# pcb-bldc-servo-2.net
KiCad netlist of a schematic drawn in EAGLE
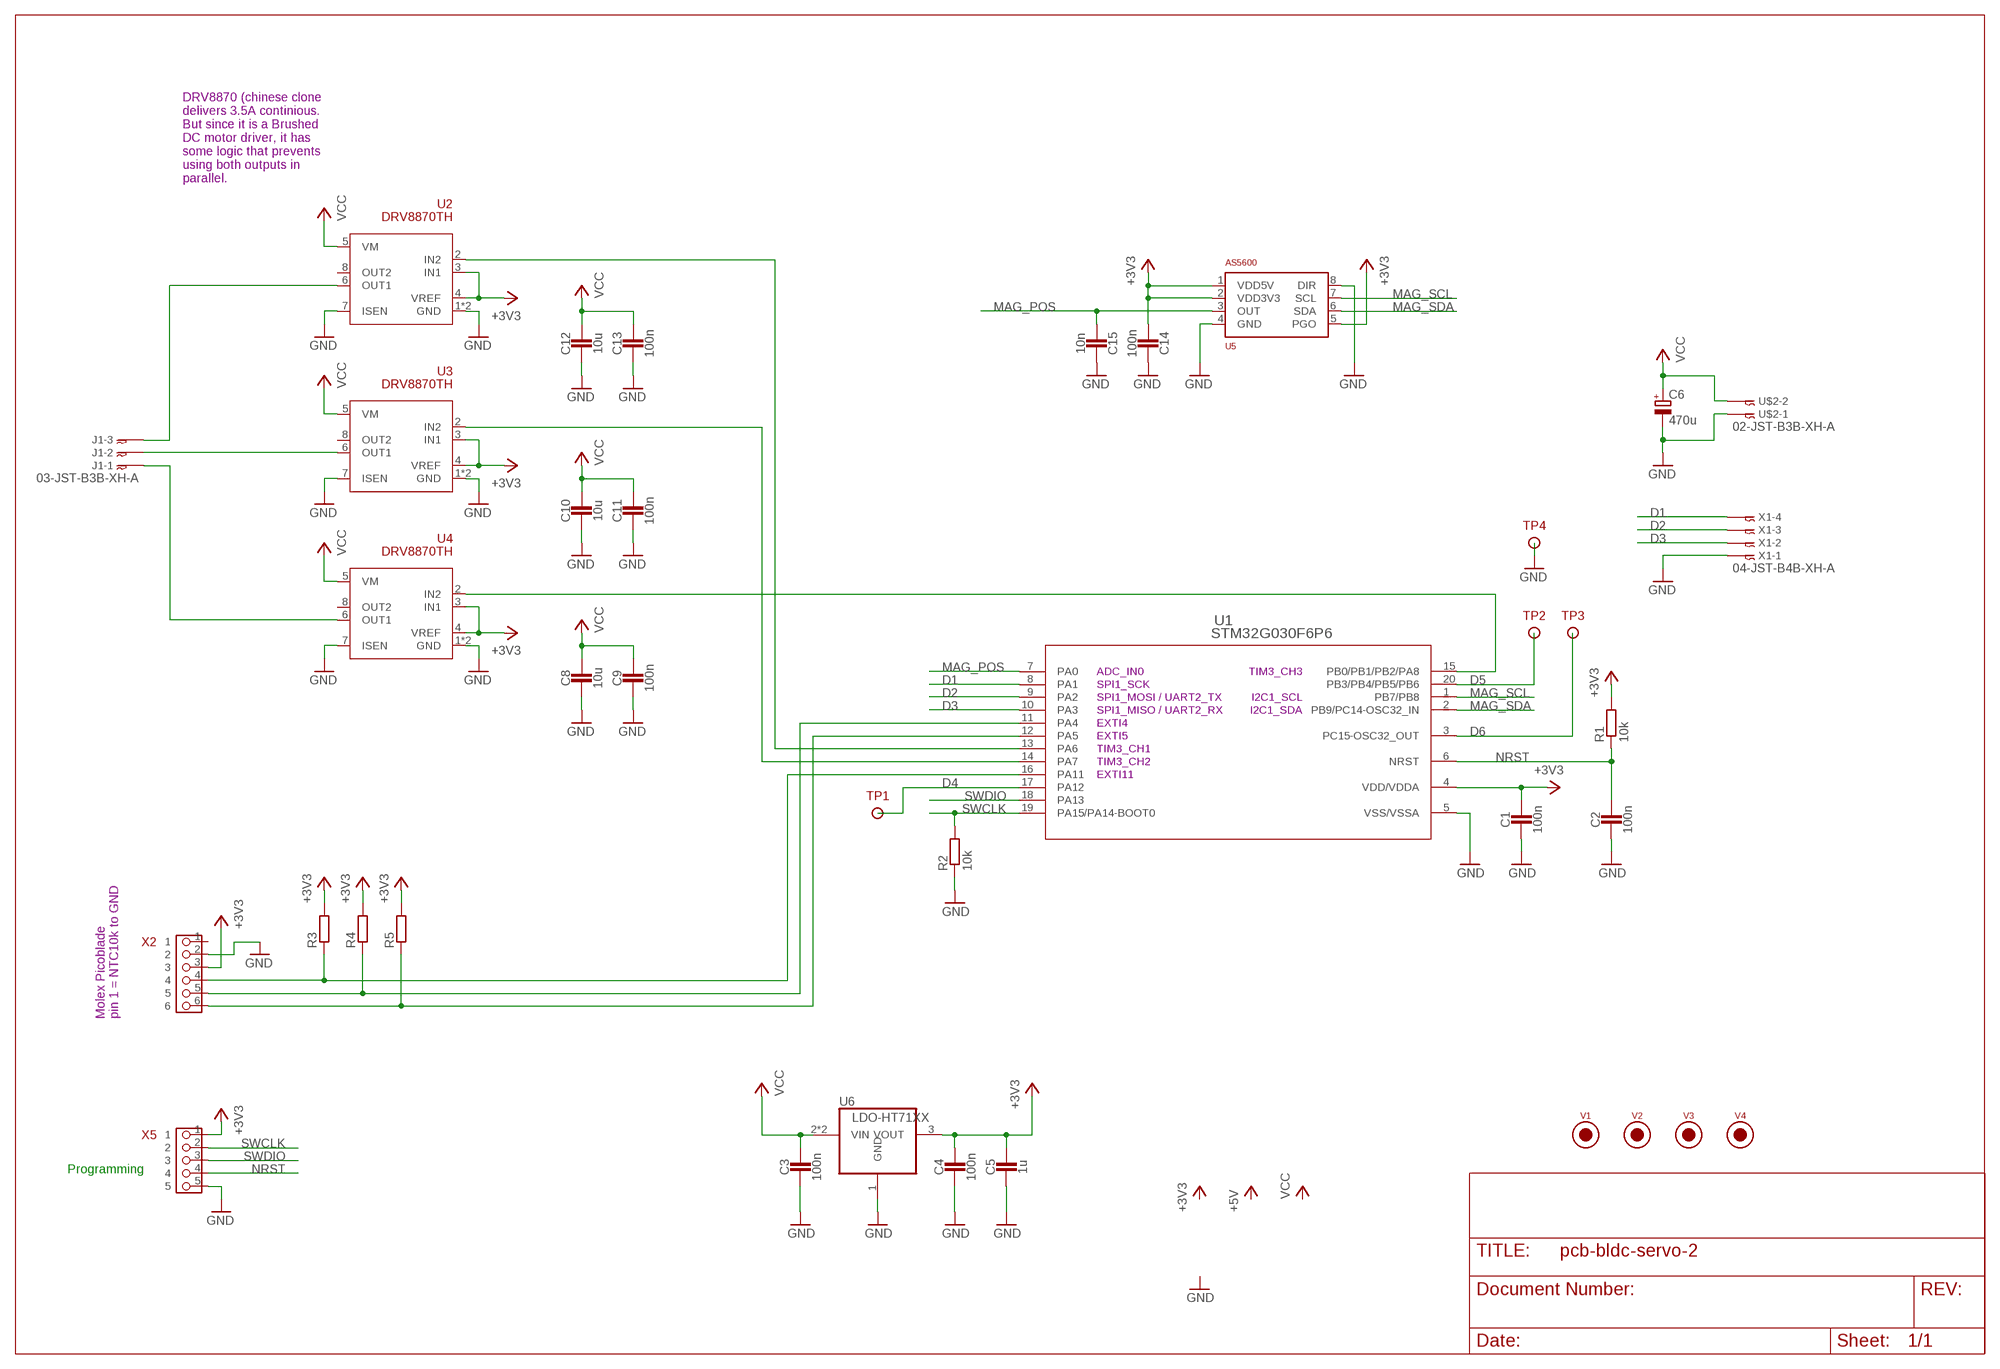
[diagram p0: schematic, sheet 1]

(export (version "E")
  (design (tool "Eeschema 10.0.6"))
  (components
    (comp (ref "C1")
      (value "100n")
      (footprint "eagle-import:0603_CAP")
      (libsource (lib "eagle-import") (part "CAPACITOR0603_CAP"))
    )
    (comp (ref "C2")
      (value "100n")
      (footprint "eagle-import:0603_CAP")
      (libsource (lib "eagle-import") (part "CAPACITOR0603_CAP"))
    )
    (comp (ref "C3")
      (value "100n")
      (footprint "eagle-import:0603_CAP")
      (libsource (lib "eagle-import") (part "CAPACITOR0603_CAP"))
    )
    (comp (ref "C4")
      (value "100n")
      (footprint "eagle-import:0603_CAP")
      (libsource (lib "eagle-import") (part "CAPACITOR0603_CAP"))
    )
    (comp (ref "C5")
      (value "1u")
      (footprint "eagle-import:0603_CAP")
      (libsource (lib "eagle-import") (part "CAPACITOR0603_CAP"))
    )
    (comp (ref "C6")
      (value "470u")
      (footprint "eagle-import:153CLV-1010")
      (libsource (lib "eagle-import") (part "CPOL-EU153CLV-1010"))
    )
    (comp (ref "C8")
      (value "10u")
      (footprint "eagle-import:1206_CAP")
      (libsource (lib "eagle-import") (part "CAPACITOR1206_CAP"))
    )
    (comp (ref "C9")
      (value "100n")
      (footprint "eagle-import:0603_CAP")
      (libsource (lib "eagle-import") (part "CAPACITOR0603_CAP"))
    )
    (comp (ref "C10")
      (value "10u")
      (footprint "eagle-import:1206_CAP")
      (libsource (lib "eagle-import") (part "CAPACITOR1206_CAP"))
    )
    (comp (ref "C11")
      (value "100n")
      (footprint "eagle-import:0603_CAP")
      (libsource (lib "eagle-import") (part "CAPACITOR0603_CAP"))
    )
    (comp (ref "C12")
      (value "10u")
      (footprint "eagle-import:1206_CAP")
      (libsource (lib "eagle-import") (part "CAPACITOR1206_CAP"))
    )
    (comp (ref "C13")
      (value "100n")
      (footprint "eagle-import:0603_CAP")
      (libsource (lib "eagle-import") (part "CAPACITOR0603_CAP"))
    )
    (comp (ref "C14")
      (value "100n")
      (footprint "eagle-import:0603_CAP")
      (libsource (lib "eagle-import") (part "CAPACITOR0603_CAP"))
    )
    (comp (ref "C15")
      (value "10n")
      (footprint "eagle-import:0603_CAP")
      (libsource (lib "eagle-import") (part "CAPACITOR0603_CAP"))
    )
    (comp (ref "J1")
      (value "03-JST-B3B-XH-A")
      (footprint "eagle-import:B3B-XH")
      (libsource (lib "eagle-import") (part "03-JST-B3B-XH-A"))
    )
    (comp (ref "R1")
      (value "10k")
      (footprint "eagle-import:0603-RES")
      (libsource (lib "eagle-import") (part "RESISTOR0603_RES"))
    )
    (comp (ref "R2")
      (value "10k")
      (footprint "eagle-import:0603-RES")
      (libsource (lib "eagle-import") (part "RESISTOR0603_RES"))
    )
    (comp (ref "R3")
      (value "RESISTOR0603_RES")
      (footprint "eagle-import:0603-RES")
      (libsource (lib "eagle-import") (part "RESISTOR0603_RES"))
    )
    (comp (ref "R4")
      (value "RESISTOR0603_RES")
      (footprint "eagle-import:0603-RES")
      (libsource (lib "eagle-import") (part "RESISTOR0603_RES"))
    )
    (comp (ref "R5")
      (value "RESISTOR0603_RES")
      (footprint "eagle-import:0603-RES")
      (libsource (lib "eagle-import") (part "RESISTOR0603_RES"))
    )
    (comp (ref "TP1")
      (value "TESTPIN1MM")
      (footprint "eagle-import:PIN-SMD-1X1-TEST_1M0")
      (libsource (lib "eagle-import") (part "TESTPIN1MM"))
    )
    (comp (ref "TP2")
      (value "TESTPIN1MM")
      (footprint "eagle-import:PIN-SMD-1X1-TEST_1M0")
      (libsource (lib "eagle-import") (part "TESTPIN1MM"))
    )
    (comp (ref "TP3")
      (value "TESTPIN1MM")
      (footprint "eagle-import:PIN-SMD-1X1-TEST_1M0")
      (libsource (lib "eagle-import") (part "TESTPIN1MM"))
    )
    (comp (ref "TP4")
      (value "TESTPIN1MM")
      (footprint "eagle-import:PIN-SMD-1X1-TEST_1M0")
      (libsource (lib "eagle-import") (part "TESTPIN1MM"))
    )
    (comp (ref "U$2")
      (value "02-JST-B3B-XH-A")
      (footprint "eagle-import:B2B-XH")
      (libsource (lib "eagle-import") (part "02-JST-B3B-XH-A"))
    )
    (comp (ref "U1")
      (value "STM32G030F6P6")
      (footprint "eagle-import:TSSOP20")
      (fields (field (name "COPYRIGHT") "Copyright (C) 2024 Ultra Librarian. All rights reserved."))
      (libsource (lib "eagle-import") (part "STM32G030F6P6"))
    )
    (comp (ref "U2")
      (value "DRV8870TH")
      (footprint "eagle-import:SOIC-8-THERM")
      (libsource (lib "eagle-import") (part "DRV8870TH"))
    )
    (comp (ref "U3")
      (value "DRV8870TH")
      (footprint "eagle-import:SOIC-8-THERM")
      (libsource (lib "eagle-import") (part "DRV8870TH"))
    )
    (comp (ref "U4")
      (value "DRV8870TH")
      (footprint "eagle-import:SOIC-8-THERM")
      (libsource (lib "eagle-import") (part "DRV8870TH"))
    )
    (comp (ref "U5")
      (value "AS5600")
      (footprint "eagle-import:SOIC-8")
      (libsource (lib "eagle-import") (part "AS5600"))
    )
    (comp (ref "U6")
      (value "LDO-HT71XX")
      (footprint "eagle-import:SOT-89")
      (libsource (lib "eagle-import") (part "LDO-HT71XX"))
    )
    (comp (ref "V1")
      (value "FIDUCIAL2MM")
      (footprint "eagle-import:FIDUCIAL_2MM")
      (libsource (lib "eagle-import") (part "FIDUCIAL2MM"))
    )
    (comp (ref "V2")
      (value "FIDUCIAL2MM")
      (footprint "eagle-import:FIDUCIAL_2MM")
      (libsource (lib "eagle-import") (part "FIDUCIAL2MM"))
    )
    (comp (ref "V3")
      (value "FIDUCIAL2MM")
      (footprint "eagle-import:FIDUCIAL_2MM")
      (libsource (lib "eagle-import") (part "FIDUCIAL2MM"))
    )
    (comp (ref "V4")
      (value "FIDUCIAL2MM")
      (footprint "eagle-import:FIDUCIAL_2MM")
      (libsource (lib "eagle-import") (part "FIDUCIAL2MM"))
    )
    (comp (ref "X1")
      (value "04-JST-B4B-XH-A")
      (footprint "eagle-import:B4B-XH")
      (libsource (lib "eagle-import") (part "04-JST-B4B-XH-A"))
    )
    (comp (ref "X2")
      (value "PIN_6X1")
      (footprint "eagle-import:PIN_6X1_MOLEX_PICOBLADE")
      (libsource (lib "eagle-import") (part "PIN_6X1"))
    )
    (comp (ref "X5")
      (value "PIN_5X1HD")
      (footprint "eagle-import:PIN_5X1_HD")
      (libsource (lib "eagle-import") (part "PIN_5X1HD"))
    )
  )
  (nets
    (net (code "1") (name "+3V3") (class "Default")
      (node (ref "C1") (pin "1") (pinfunction "1_1") (pintype "bidirectional"))
      (node (ref "C14") (pin "1") (pinfunction "1_1") (pintype "bidirectional"))
      (node (ref "C4") (pin "1") (pinfunction "1_1") (pintype "bidirectional"))
      (node (ref "C5") (pin "1") (pinfunction "1_1") (pintype "bidirectional"))
      (node (ref "R1") (pin "2") (pinfunction "2_2") (pintype "passive"))
      (node (ref "R3") (pin "2") (pinfunction "2_2") (pintype "passive"))
      (node (ref "R4") (pin "2") (pinfunction "2_2") (pintype "passive"))
      (node (ref "R5") (pin "2") (pinfunction "2_2") (pintype "passive"))
      (node (ref "U1") (pin "4") (pinfunction "VDD/VDDA_4") (pintype "power_in"))
      (node (ref "U2") (pin "3") (pinfunction "IN1_3") (pintype "bidirectional"))
      (node (ref "U2") (pin "4") (pinfunction "VREF_4") (pintype "bidirectional"))
      (node (ref "U3") (pin "3") (pinfunction "IN1_3") (pintype "bidirectional"))
      (node (ref "U3") (pin "4") (pinfunction "VREF_4") (pintype "bidirectional"))
      (node (ref "U4") (pin "3") (pinfunction "IN1_3") (pintype "bidirectional"))
      (node (ref "U4") (pin "4") (pinfunction "VREF_4") (pintype "bidirectional"))
      (node (ref "U5") (pin "1") (pinfunction "VDD5V_1") (pintype "bidirectional"))
      (node (ref "U5") (pin "2") (pinfunction "VDD3V3_2") (pintype "bidirectional"))
      (node (ref "U5") (pin "5") (pinfunction "PGO_5") (pintype "bidirectional"))
      (node (ref "U6") (pin "3") (pinfunction "VOUT_3") (pintype "output"))
      (node (ref "X2") (pin "3") (pinfunction "3_3") (pintype "bidirectional"))
      (node (ref "X5") (pin "1") (pinfunction "1_1") (pintype "bidirectional"))
    )
    (net (code "3") (name "/D1") (class "Default")
      (node (ref "U1") (pin "8") (pinfunction "PA1_8") (pintype "bidirectional"))
      (node (ref "X1") (pin "P$4") (pinfunction "1_P$4") (pintype "passive"))
    )
    (net (code "4") (name "/D2") (class "Default")
      (node (ref "U1") (pin "9") (pinfunction "PA2_9") (pintype "bidirectional"))
      (node (ref "X1") (pin "P$3") (pinfunction "1_P$3") (pintype "passive"))
    )
    (net (code "5") (name "/D3") (class "Default")
      (node (ref "U1") (pin "10") (pinfunction "PA3_10") (pintype "bidirectional"))
      (node (ref "X1") (pin "P$2") (pinfunction "1_P$2") (pintype "passive"))
    )
    (net (code "6") (name "/D4") (class "Default")
      (node (ref "TP1") (pin "1") (pinfunction "1_1") (pintype "bidirectional"))
      (node (ref "U1") (pin "17") (pinfunction "PA12_17") (pintype "bidirectional"))
    )
    (net (code "7") (name "/D5") (class "Default")
      (node (ref "TP2") (pin "1") (pinfunction "1_1") (pintype "bidirectional"))
      (node (ref "U1") (pin "20") (pinfunction "PB3/PB4/PB5/PB6_20") (pintype "bidirectional"))
    )
    (net (code "8") (name "/D6") (class "Default")
      (node (ref "TP3") (pin "1") (pinfunction "1_1") (pintype "bidirectional"))
      (node (ref "U1") (pin "3") (pinfunction "PC15-OSC32_OUT_3") (pintype "bidirectional"))
    )
    (net (code "9") (name "/MAG_POS") (class "Default")
      (node (ref "C15") (pin "1") (pinfunction "1_1") (pintype "bidirectional"))
      (node (ref "U1") (pin "7") (pinfunction "PA0_7") (pintype "bidirectional"))
      (node (ref "U5") (pin "3") (pinfunction "OUT_3") (pintype "bidirectional"))
    )
    (net (code "10") (name "/MAG_SCL") (class "Default")
      (node (ref "U1") (pin "1") (pinfunction "PB7/PB8_1") (pintype "bidirectional"))
      (node (ref "U5") (pin "7") (pinfunction "SCL_7") (pintype "bidirectional"))
    )
    (net (code "11") (name "/MAG_SDA") (class "Default")
      (node (ref "U1") (pin "2") (pinfunction "PB9/PC14-OSC32_IN_2") (pintype "bidirectional"))
      (node (ref "U5") (pin "6") (pinfunction "SDA_6") (pintype "bidirectional"))
    )
    (net (code "12") (name "/NRST") (class "Default")
      (node (ref "C2") (pin "1") (pinfunction "1_1") (pintype "bidirectional"))
      (node (ref "R1") (pin "1") (pinfunction "1_1") (pintype "passive"))
      (node (ref "U1") (pin "6") (pinfunction "NRST_6") (pintype "bidirectional"))
      (node (ref "X5") (pin "4") (pinfunction "4_4") (pintype "bidirectional"))
    )
    (net (code "13") (name "/SWCLK") (class "Default")
      (node (ref "R2") (pin "2") (pinfunction "2_2") (pintype "passive"))
      (node (ref "U1") (pin "19") (pinfunction "PA15/PA14-BOOT0_19") (pintype "bidirectional"))
      (node (ref "X5") (pin "2") (pinfunction "2_2") (pintype "bidirectional"))
    )
    (net (code "14") (name "/SWDIO") (class "Default")
      (node (ref "U1") (pin "18") (pinfunction "PA13_18") (pintype "bidirectional"))
      (node (ref "X5") (pin "3") (pinfunction "3_3") (pintype "bidirectional"))
    )
    (net (code "15") (name "GND") (class "Default")
      (node (ref "C1") (pin "2") (pinfunction "2_2") (pintype "bidirectional"))
      (node (ref "C10") (pin "2") (pinfunction "2_2") (pintype "bidirectional"))
      (node (ref "C11") (pin "2") (pinfunction "2_2") (pintype "bidirectional"))
      (node (ref "C12") (pin "2") (pinfunction "2_2") (pintype "bidirectional"))
      (node (ref "C13") (pin "2") (pinfunction "2_2") (pintype "bidirectional"))
      (node (ref "C14") (pin "2") (pinfunction "2_2") (pintype "bidirectional"))
      (node (ref "C15") (pin "2") (pinfunction "2_2") (pintype "bidirectional"))
      (node (ref "C2") (pin "2") (pinfunction "2_2") (pintype "bidirectional"))
      (node (ref "C3") (pin "2") (pinfunction "2_2") (pintype "bidirectional"))
      (node (ref "C4") (pin "2") (pinfunction "2_2") (pintype "bidirectional"))
      (node (ref "C5") (pin "2") (pinfunction "2_2") (pintype "bidirectional"))
      (node (ref "C6") (pin "-") (pinfunction "-_-") (pintype "passive"))
      (node (ref "C8") (pin "2") (pinfunction "2_2") (pintype "bidirectional"))
      (node (ref "C9") (pin "2") (pinfunction "2_2") (pintype "bidirectional"))
      (node (ref "R2") (pin "1") (pinfunction "1_1") (pintype "passive"))
      (node (ref "TP4") (pin "1") (pinfunction "1_1") (pintype "bidirectional"))
      (node (ref "U$2") (pin "P$1") (pinfunction "1_P$1") (pintype "passive"))
      (node (ref "U1") (pin "5") (pinfunction "VSS/VSSA_5") (pintype "power_in"))
      (node (ref "U2") (pin "1") (pinfunction "GND_1") (pintype "bidirectional"))
      (node (ref "U2") (pin "7") (pinfunction "ISEN_7") (pintype "bidirectional"))
      (node (ref "U2") (pin "9") (pinfunction "GND_9") (pintype "bidirectional"))
      (node (ref "U3") (pin "1") (pinfunction "GND_1") (pintype "bidirectional"))
      (node (ref "U3") (pin "7") (pinfunction "ISEN_7") (pintype "bidirectional"))
      (node (ref "U3") (pin "9") (pinfunction "GND_9") (pintype "bidirectional"))
      (node (ref "U4") (pin "1") (pinfunction "GND_1") (pintype "bidirectional"))
      (node (ref "U4") (pin "7") (pinfunction "ISEN_7") (pintype "bidirectional"))
      (node (ref "U4") (pin "9") (pinfunction "GND_9") (pintype "bidirectional"))
      (node (ref "U5") (pin "4") (pinfunction "GND_4") (pintype "bidirectional"))
      (node (ref "U5") (pin "8") (pinfunction "DIR_8") (pintype "bidirectional"))
      (node (ref "U6") (pin "1") (pinfunction "GND_1") (pintype "power_in"))
      (node (ref "X1") (pin "P$1") (pinfunction "1_P$1") (pintype "passive"))
      (node (ref "X2") (pin "2") (pinfunction "2_2") (pintype "bidirectional"))
      (node (ref "X5") (pin "5") (pinfunction "5_5") (pintype "bidirectional"))
    )
    (net (code "16") (name "Net-(J1A-1)") (class "Default")
      (node (ref "J1") (pin "P$1") (pinfunction "1_P$1") (pintype "passive"))
      (node (ref "U4") (pin "6") (pinfunction "OUT1_6") (pintype "bidirectional"))
    )
    (net (code "17") (name "Net-(J1B-1)") (class "Default")
      (node (ref "J1") (pin "P$2") (pinfunction "1_P$2") (pintype "passive"))
      (node (ref "U3") (pin "6") (pinfunction "OUT1_6") (pintype "bidirectional"))
    )
    (net (code "18") (name "Net-(J1C-1)") (class "Default")
      (node (ref "J1") (pin "P$3") (pinfunction "1_P$3") (pintype "passive"))
      (node (ref "U2") (pin "6") (pinfunction "OUT1_6") (pintype "bidirectional"))
    )
    (net (code "19") (name "Net-(U1-PA4)") (class "Default")
      (node (ref "R4") (pin "1") (pinfunction "1_1") (pintype "passive"))
      (node (ref "U1") (pin "11") (pinfunction "PA4_11") (pintype "bidirectional"))
      (node (ref "X2") (pin "5") (pinfunction "5_5") (pintype "bidirectional"))
    )
    (net (code "20") (name "Net-(U1-PA5)") (class "Default")
      (node (ref "R5") (pin "1") (pinfunction "1_1") (pintype "passive"))
      (node (ref "U1") (pin "12") (pinfunction "PA5_12") (pintype "bidirectional"))
      (node (ref "X2") (pin "6") (pinfunction "6_6") (pintype "bidirectional"))
    )
    (net (code "21") (name "Net-(U1-PA6)") (class "Default")
      (node (ref "U1") (pin "13") (pinfunction "PA6_13") (pintype "bidirectional"))
      (node (ref "U2") (pin "2") (pinfunction "IN2_2") (pintype "bidirectional"))
    )
    (net (code "22") (name "Net-(U1-PA7)") (class "Default")
      (node (ref "U1") (pin "14") (pinfunction "PA7_14") (pintype "bidirectional"))
      (node (ref "U3") (pin "2") (pinfunction "IN2_2") (pintype "bidirectional"))
    )
    (net (code "23") (name "Net-(U1-PA11)") (class "Default")
      (node (ref "R3") (pin "1") (pinfunction "1_1") (pintype "passive"))
      (node (ref "U1") (pin "16") (pinfunction "PA11_16") (pintype "bidirectional"))
      (node (ref "X2") (pin "4") (pinfunction "4_4") (pintype "bidirectional"))
    )
    (net (code "24") (name "Net-(U1-PB0{slash}PB1{slash}PB2{slash}PA8)") (class "Default")
      (node (ref "U1") (pin "15") (pinfunction "PB0/PB1/PB2/PA8_15") (pintype "bidirectional"))
      (node (ref "U4") (pin "2") (pinfunction "IN2_2") (pintype "bidirectional"))
    )
    (net (code "25") (name "VCC") (class "Default")
      (node (ref "C10") (pin "1") (pinfunction "1_1") (pintype "bidirectional"))
      (node (ref "C11") (pin "1") (pinfunction "1_1") (pintype "bidirectional"))
      (node (ref "C12") (pin "1") (pinfunction "1_1") (pintype "bidirectional"))
      (node (ref "C13") (pin "1") (pinfunction "1_1") (pintype "bidirectional"))
      (node (ref "C3") (pin "1") (pinfunction "1_1") (pintype "bidirectional"))
      (node (ref "C6") (pin "+") (pinfunction "+_+") (pintype "passive"))
      (node (ref "C8") (pin "1") (pinfunction "1_1") (pintype "bidirectional"))
      (node (ref "C9") (pin "1") (pinfunction "1_1") (pintype "bidirectional"))
      (node (ref "U$2") (pin "P$2") (pinfunction "1_P$2") (pintype "passive"))
      (node (ref "U2") (pin "5") (pinfunction "VM_5") (pintype "bidirectional"))
      (node (ref "U3") (pin "5") (pinfunction "VM_5") (pintype "bidirectional"))
      (node (ref "U4") (pin "5") (pinfunction "VM_5") (pintype "bidirectional"))
      (node (ref "U6") (pin "2") (pinfunction "VIN_2") (pintype "input"))
      (node (ref "U6") (pin "2@1") (pinfunction "VIN_2@1") (pintype "input"))
    )
    (net (code "26") (name "unconnected-(U2-OUT2-Pad8)") (class "Default")
      (node (ref "U2") (pin "8") (pinfunction "OUT2_8") (pintype "bidirectional"))
    )
    (net (code "27") (name "unconnected-(U3-OUT2-Pad8)") (class "Default")
      (node (ref "U3") (pin "8") (pinfunction "OUT2_8") (pintype "bidirectional"))
    )
    (net (code "28") (name "unconnected-(U4-OUT2-Pad8)") (class "Default")
      (node (ref "U4") (pin "8") (pinfunction "OUT2_8") (pintype "bidirectional"))
    )
    (net (code "29") (name "unconnected-(X2-Pad1)") (class "Default")
      (node (ref "X2") (pin "1") (pinfunction "1_1") (pintype "bidirectional"))
    )
  )
)
